# LB_BIT_i21_MICROPHONE-v03_rev4_4.net
KiCad netlist of a schematic drawn in EAGLE
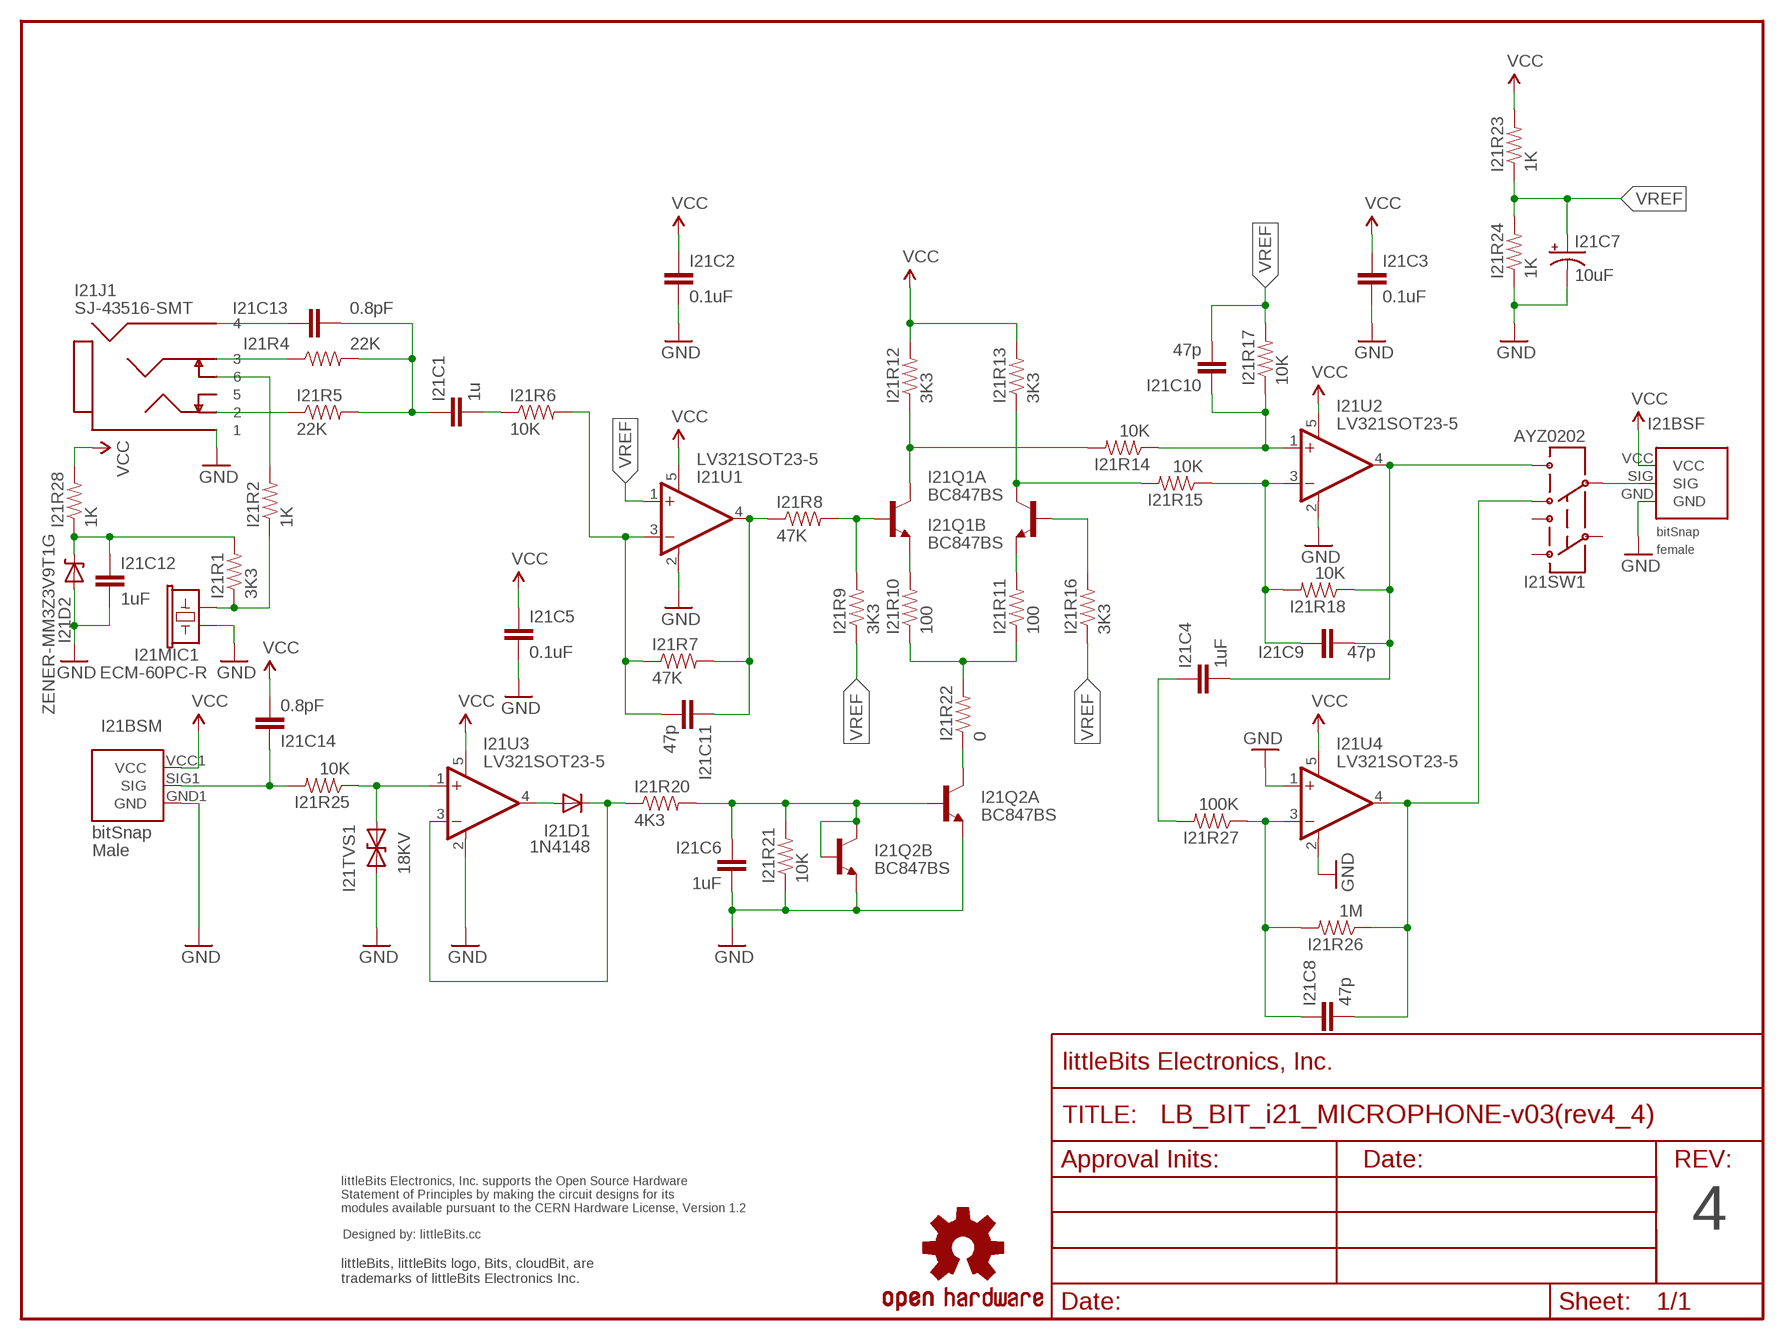
[diagram p0: schematic, sheet 1]

(export (version "E")
  (design (tool "Eeschema 10.0.6"))
  (components
    (comp (ref "I21BSF")
      (value "BITSNAP_V03_FEMALE")
      (footprint "eagle-import:BITSNAP_V03_FEMALE")
      (libsource (lib "eagle-import") (part "BITSNAP_V03_FEMALE"))
    )
    (comp (ref "I21BSM")
      (value "BITSNAP_V03_MALE")
      (footprint "eagle-import:BITSNAP_V03_MALE")
      (libsource (lib "eagle-import") (part "BITSNAP_V03_MALE"))
    )
    (comp (ref "I21C1")
      (value "1u")
      (footprint "eagle-import:CAP-0603")
      (libsource (lib "eagle-import") (part "CAPCAP-0603"))
    )
    (comp (ref "I21C2")
      (value "0.1uF")
      (footprint "eagle-import:CAP-0603")
      (libsource (lib "eagle-import") (part "CAPCAP-0603"))
    )
    (comp (ref "I21C3")
      (value "0.1uF")
      (footprint "eagle-import:CAP-0603")
      (libsource (lib "eagle-import") (part "CAPCAP-0603"))
    )
    (comp (ref "I21C4")
      (value "1uF")
      (footprint "eagle-import:CAP-0603")
      (libsource (lib "eagle-import") (part "CAPCAP-0603"))
    )
    (comp (ref "I21C5")
      (value "0.1uF")
      (footprint "eagle-import:CAP-0603")
      (libsource (lib "eagle-import") (part "CAPCAP-0603"))
    )
    (comp (ref "I21C6")
      (value "1uF")
      (footprint "eagle-import:CAP-0603")
      (libsource (lib "eagle-import") (part "CAPCAP-0603"))
    )
    (comp (ref "I21C7")
      (value "10uF")
      (footprint "eagle-import:EIA3216")
      (libsource (lib "eagle-import") (part "CAP_POL3216"))
    )
    (comp (ref "I21C8")
      (value "47p")
      (footprint "eagle-import:CAP-0603")
      (libsource (lib "eagle-import") (part "CAPCAP-0603"))
    )
    (comp (ref "I21C9")
      (value "47p")
      (footprint "eagle-import:CAP-0603")
      (libsource (lib "eagle-import") (part "CAPCAP-0603"))
    )
    (comp (ref "I21C10")
      (value "47p")
      (footprint "eagle-import:CAP-0603")
      (libsource (lib "eagle-import") (part "CAPCAP-0603"))
    )
    (comp (ref "I21C11")
      (value "47p")
      (footprint "eagle-import:CAP-0603")
      (libsource (lib "eagle-import") (part "CAPCAP-0603"))
    )
    (comp (ref "I21C12")
      (value "1uF")
      (footprint "eagle-import:CAP-0603")
      (libsource (lib "eagle-import") (part "CAPCAP-0603"))
    )
    (comp (ref "I21C13")
      (value "0.8pF")
      (footprint "eagle-import:CAP-0603")
      (libsource (lib "eagle-import") (part "CAPCAP-0603"))
    )
    (comp (ref "I21C14")
      (value "0.8pF")
      (footprint "eagle-import:CAP-0603")
      (libsource (lib "eagle-import") (part "CAPCAP-0603"))
    )
    (comp (ref "I21D1")
      (value "1N4148")
      (footprint "eagle-import:SOD-323")
      (libsource (lib "eagle-import") (part "DIODESOD"))
    )
    (comp (ref "I21D2")
      (value "ZENER-MM3Z3V9T1G")
      (footprint "eagle-import:SOD-323")
      (libsource (lib "eagle-import") (part "DIODE-ZENER-BZT52"))
    )
    (comp (ref "I21J1")
      (value "SJ-43516-SMT")
      (footprint "eagle-import:CUI-SJ-4351")
      (libsource (lib "eagle-import") (part "JACK-PHONO-4COND-SW"))
    )
    (comp (ref "I21MIC1")
      (value "ECM-60PC-R")
      (footprint "eagle-import:MIC9.7MM")
      (libsource (lib "eagle-import") (part "MIC9.7MM"))
    )
    (comp (ref "I21Q1")
      (value "BC847BS")
      (footprint "eagle-import:SOT-363_PHILLIPS")
      (libsource (lib "eagle-import") (part "TRANS-BJT_NPN-DUAL-BC847BS"))
    )
    (comp (ref "I21Q2")
      (value "BC847BS")
      (footprint "eagle-import:SOT-363_PHILLIPS")
      (libsource (lib "eagle-import") (part "TRANS-BJT_NPN-DUAL-BC847BS"))
    )
    (comp (ref "I21R1")
      (value "3K3")
      (footprint "eagle-import:RES-0603")
      (libsource (lib "eagle-import") (part "RESISTOR0603"))
    )
    (comp (ref "I21R2")
      (value "1K")
      (footprint "eagle-import:RES-0603")
      (libsource (lib "eagle-import") (part "RESISTOR0603"))
    )
    (comp (ref "I21R4")
      (value "22K")
      (footprint "eagle-import:RES-0603")
      (libsource (lib "eagle-import") (part "RESISTOR0603"))
    )
    (comp (ref "I21R5")
      (value "22K")
      (footprint "eagle-import:RES-0603")
      (libsource (lib "eagle-import") (part "RESISTOR0603"))
    )
    (comp (ref "I21R6")
      (value "10K")
      (footprint "eagle-import:RES-0603")
      (libsource (lib "eagle-import") (part "RESISTOR0603"))
    )
    (comp (ref "I21R7")
      (value "47K")
      (footprint "eagle-import:RES-0603")
      (libsource (lib "eagle-import") (part "RESISTOR0603"))
    )
    (comp (ref "I21R8")
      (value "47K")
      (footprint "eagle-import:RES-0603")
      (libsource (lib "eagle-import") (part "RESISTOR0603"))
    )
    (comp (ref "I21R9")
      (value "3K3")
      (footprint "eagle-import:RES-0603")
      (libsource (lib "eagle-import") (part "RESISTOR0603"))
    )
    (comp (ref "I21R10")
      (value "100")
      (footprint "eagle-import:RES-0603")
      (libsource (lib "eagle-import") (part "RESISTOR0603"))
    )
    (comp (ref "I21R11")
      (value "100")
      (footprint "eagle-import:RES-0603")
      (libsource (lib "eagle-import") (part "RESISTOR0603"))
    )
    (comp (ref "I21R12")
      (value "3K3")
      (footprint "eagle-import:RES-0603")
      (libsource (lib "eagle-import") (part "RESISTOR0603"))
    )
    (comp (ref "I21R13")
      (value "3K3")
      (footprint "eagle-import:RES-0603")
      (libsource (lib "eagle-import") (part "RESISTOR0603"))
    )
    (comp (ref "I21R14")
      (value "10K")
      (footprint "eagle-import:RES-0603")
      (libsource (lib "eagle-import") (part "RESISTOR0603"))
    )
    (comp (ref "I21R15")
      (value "10K")
      (footprint "eagle-import:RES-0603")
      (libsource (lib "eagle-import") (part "RESISTOR0603"))
    )
    (comp (ref "I21R16")
      (value "3K3")
      (footprint "eagle-import:RES-0603")
      (libsource (lib "eagle-import") (part "RESISTOR0603"))
    )
    (comp (ref "I21R17")
      (value "10K")
      (footprint "eagle-import:RES-0603")
      (libsource (lib "eagle-import") (part "RESISTOR0603"))
    )
    (comp (ref "I21R18")
      (value "10K")
      (footprint "eagle-import:RES-0603")
      (libsource (lib "eagle-import") (part "RESISTOR0603"))
    )
    (comp (ref "I21R20")
      (value "4K3")
      (footprint "eagle-import:RES-0603")
      (libsource (lib "eagle-import") (part "RESISTOR0603"))
    )
    (comp (ref "I21R21")
      (value "10K")
      (footprint "eagle-import:RES-0603")
      (libsource (lib "eagle-import") (part "RESISTOR0603"))
    )
    (comp (ref "I21R22")
      (value "0")
      (footprint "eagle-import:RES-0603")
      (libsource (lib "eagle-import") (part "RESISTOR0603"))
    )
    (comp (ref "I21R23")
      (value "1K")
      (footprint "eagle-import:RES-0603")
      (libsource (lib "eagle-import") (part "RESISTOR0603"))
    )
    (comp (ref "I21R24")
      (value "1K")
      (footprint "eagle-import:RES-0603")
      (libsource (lib "eagle-import") (part "RESISTOR0603"))
    )
    (comp (ref "I21R25")
      (value "10K")
      (footprint "eagle-import:RES-0603")
      (libsource (lib "eagle-import") (part "RESISTOR0603"))
    )
    (comp (ref "I21R26")
      (value "1M")
      (footprint "eagle-import:RES-0603")
      (libsource (lib "eagle-import") (part "RESISTOR0603"))
    )
    (comp (ref "I21R27")
      (value "100K")
      (footprint "eagle-import:RES-0603")
      (libsource (lib "eagle-import") (part "RESISTOR0603"))
    )
    (comp (ref "I21R28")
      (value "1K")
      (footprint "eagle-import:RES-0603")
      (libsource (lib "eagle-import") (part "RESISTOR0603"))
    )
    (comp (ref "I21SW1")
      (value "AYZ0202")
      (footprint "eagle-import:AYZ0202")
      (libsource (lib "eagle-import") (part "AYZ0202"))
    )
    (comp (ref "I21TVS1")
      (value "18KV")
      (footprint "eagle-import:SOD-923")
      (fields (field (name "MPN") "ESD9B5.0ST5G"))
      (libsource (lib "eagle-import") (part "DIODE-TVSSOD-923"))
    )
    (comp (ref "I21U1")
      (value "LV321SOT23-5")
      (footprint "eagle-import:SOT23-5")
      (libsource (lib "eagle-import") (part "LV321SOT23-5"))
    )
    (comp (ref "I21U2")
      (value "LV321SOT23-5")
      (footprint "eagle-import:SOT23-5")
      (libsource (lib "eagle-import") (part "LV321SOT23-5"))
    )
    (comp (ref "I21U3")
      (value "LV321SOT23-5")
      (footprint "eagle-import:SOT23-5")
      (libsource (lib "eagle-import") (part "LV321SOT23-5"))
    )
    (comp (ref "I21U4")
      (value "LV321SOT23-5")
      (footprint "eagle-import:SOT23-5")
      (libsource (lib "eagle-import") (part "LV321SOT23-5"))
    )
    (comp (ref "U$3")
      (value "OSHWCREDIT")
      (footprint "eagle-import:OSHWCREDIT")
      (libsource (lib "eagle-import") (part "OSHWCREDIT"))
    )
    (comp (ref "U$4")
      (value "FRAME-LETTER-OHWOHW")
      (footprint "eagle-import:FABDWG01-OHW")
      (libsource (lib "eagle-import") (part "FRAME-LETTER-OHWOHW"))
    )
    (comp (ref "U$19")
      (value "OSHW-LOGOL")
      (footprint "eagle-import:OSHW-LOGO-L")
      (libsource (lib "eagle-import") (part "OSHW-LOGOL"))
    )
  )
  (nets
    (net (code "1") (name "GND") (class "Default")
      (node (ref "I21BSF") (pin "GND") (pinfunction "GND_GND") (pintype "bidirectional"))
      (node (ref "I21BSM") (pin "GND1") (pinfunction "GND_GND1") (pintype "bidirectional"))
      (node (ref "I21C12") (pin "2") (pinfunction "2_2") (pintype "passive"))
      (node (ref "I21C2") (pin "2") (pinfunction "2_2") (pintype "passive"))
      (node (ref "I21C3") (pin "2") (pinfunction "2_2") (pintype "passive"))
      (node (ref "I21C5") (pin "2") (pinfunction "2_2") (pintype "passive"))
      (node (ref "I21C6") (pin "2") (pinfunction "2_2") (pintype "passive"))
      (node (ref "I21C7") (pin "-") (pinfunction "-_-") (pintype "passive"))
      (node (ref "I21D2") (pin "2") (pinfunction "A_2") (pintype "passive"))
      (node (ref "I21J1") (pin "1") (pinfunction "1_1") (pintype "bidirectional"))
      (node (ref "I21MIC1") (pin "2") (pinfunction "2_2") (pintype "passive"))
      (node (ref "I21Q2") (pin "1") (pinfunction "E_1") (pintype "passive"))
      (node (ref "I21Q2") (pin "4") (pinfunction "E_4") (pintype "passive"))
      (node (ref "I21R21") (pin "1") (pinfunction "1_1") (pintype "passive"))
      (node (ref "I21R24") (pin "1") (pinfunction "1_1") (pintype "passive"))
      (node (ref "I21TVS1") (pin "1") (pinfunction "A_1") (pintype "passive"))
      (node (ref "I21U1") (pin "2") (pinfunction "V-_2") (pintype "power_in"))
      (node (ref "I21U2") (pin "2") (pinfunction "V-_2") (pintype "power_in"))
      (node (ref "I21U3") (pin "2") (pinfunction "V-_2") (pintype "power_in"))
      (node (ref "I21U4") (pin "1") (pinfunction "+IN_1") (pintype "input"))
      (node (ref "I21U4") (pin "2") (pinfunction "V-_2") (pintype "power_in"))
    )
    (net (code "2") (name "Net-(I21BSF-PadSIG)") (class "Default")
      (node (ref "I21BSF") (pin "SIG") (pinfunction "SIG_SIG") (pintype "bidirectional"))
      (node (ref "I21SW1") (pin "5") (pinfunction "5_5") (pintype "bidirectional"))
    )
    (net (code "3") (name "Net-(I21BSM-SIG)") (class "Default")
      (node (ref "I21BSM") (pin "SIG1") (pinfunction "SIG_SIG1") (pintype "bidirectional"))
      (node (ref "I21C14") (pin "1") (pinfunction "1_1") (pintype "passive"))
      (node (ref "I21R25") (pin "2") (pinfunction "2_2") (pintype "passive"))
    )
    (net (code "4") (name "Net-(I21C1-Pad1)") (class "Default")
      (node (ref "I21C1") (pin "1") (pinfunction "1_1") (pintype "passive"))
      (node (ref "I21C13") (pin "2") (pinfunction "2_2") (pintype "passive"))
      (node (ref "I21R4") (pin "2") (pinfunction "2_2") (pintype "passive"))
      (node (ref "I21R5") (pin "2") (pinfunction "2_2") (pintype "passive"))
    )
    (net (code "5") (name "Net-(I21C1-Pad2)") (class "Default")
      (node (ref "I21C1") (pin "2") (pinfunction "2_2") (pintype "passive"))
      (node (ref "I21R6") (pin "1") (pinfunction "1_1") (pintype "passive"))
    )
    (net (code "6") (name "Net-(I21C4-Pad1)") (class "Default")
      (node (ref "I21C4") (pin "1") (pinfunction "1_1") (pintype "passive"))
      (node (ref "I21R27") (pin "2") (pinfunction "2_2") (pintype "passive"))
    )
    (net (code "7") (name "Net-(I21C13-Pad1)") (class "Default")
      (node (ref "I21C13") (pin "1") (pinfunction "1_1") (pintype "passive"))
      (node (ref "I21J1") (pin "4") (pinfunction "4_4") (pintype "bidirectional"))
    )
    (net (code "8") (name "Net-(I21D1-A)") (class "Default")
      (node (ref "I21D1") (pin "2") (pinfunction "A_2") (pintype "passive"))
      (node (ref "I21U3") (pin "4") (pinfunction "OUT_4") (pintype "output"))
    )
    (net (code "9") (name "Net-(I21D1-C)") (class "Default")
      (node (ref "I21D1") (pin "1") (pinfunction "C_1") (pintype "passive"))
      (node (ref "I21R20") (pin "1") (pinfunction "1_1") (pintype "passive"))
      (node (ref "I21U3") (pin "3") (pinfunction "-IN_3") (pintype "input"))
    )
    (net (code "10") (name "Net-(I21D2-C)") (class "Default")
      (node (ref "I21C12") (pin "1") (pinfunction "1_1") (pintype "passive"))
      (node (ref "I21D2") (pin "1") (pinfunction "C_1") (pintype "passive"))
      (node (ref "I21R1") (pin "2") (pinfunction "2_2") (pintype "passive"))
      (node (ref "I21R28") (pin "1") (pinfunction "1_1") (pintype "passive"))
    )
    (net (code "11") (name "Net-(I21J1-Pad2)") (class "Default")
      (node (ref "I21J1") (pin "2") (pinfunction "2_2") (pintype "bidirectional"))
      (node (ref "I21R5") (pin "1") (pinfunction "1_1") (pintype "passive"))
    )
    (net (code "12") (name "Net-(I21J1-Pad3)") (class "Default")
      (node (ref "I21J1") (pin "3") (pinfunction "3_3") (pintype "bidirectional"))
      (node (ref "I21R4") (pin "1") (pinfunction "1_1") (pintype "passive"))
    )
    (net (code "13") (name "Net-(I21J1-Pad6)") (class "Default")
      (node (ref "I21J1") (pin "6") (pinfunction "6_6") (pintype "bidirectional"))
      (node (ref "I21R2") (pin "2") (pinfunction "2_2") (pintype "passive"))
    )
    (net (code "14") (name "Net-(I21MIC1-Pad1)") (class "Default")
      (node (ref "I21MIC1") (pin "1") (pinfunction "1_1") (pintype "passive"))
      (node (ref "I21R1") (pin "1") (pinfunction "1_1") (pintype "passive"))
      (node (ref "I21R2") (pin "1") (pinfunction "1_1") (pintype "passive"))
    )
    (net (code "15") (name "Net-(I21Q1A-B)") (class "Default")
      (node (ref "I21Q1") (pin "2") (pinfunction "B_2") (pintype "passive"))
      (node (ref "I21R8") (pin "2") (pinfunction "2_2") (pintype "passive"))
      (node (ref "I21R9") (pin "2") (pinfunction "2_2") (pintype "passive"))
    )
    (net (code "16") (name "Net-(I21Q1A-C)") (class "Default")
      (node (ref "I21Q1") (pin "6") (pinfunction "C_6") (pintype "passive"))
      (node (ref "I21R12") (pin "1") (pinfunction "1_1") (pintype "passive"))
      (node (ref "I21R14") (pin "2") (pinfunction "2_2") (pintype "passive"))
    )
    (net (code "17") (name "Net-(I21Q1A-E)") (class "Default")
      (node (ref "I21Q1") (pin "1") (pinfunction "E_1") (pintype "passive"))
      (node (ref "I21R10") (pin "2") (pinfunction "2_2") (pintype "passive"))
    )
    (net (code "18") (name "Net-(I21Q1B-B)") (class "Default")
      (node (ref "I21Q1") (pin "5") (pinfunction "B_5") (pintype "passive"))
      (node (ref "I21R16") (pin "2") (pinfunction "2_2") (pintype "passive"))
    )
    (net (code "19") (name "Net-(I21Q1B-C)") (class "Default")
      (node (ref "I21Q1") (pin "3") (pinfunction "C_3") (pintype "passive"))
      (node (ref "I21R13") (pin "1") (pinfunction "1_1") (pintype "passive"))
      (node (ref "I21R15") (pin "2") (pinfunction "2_2") (pintype "passive"))
    )
    (net (code "20") (name "Net-(I21Q1B-E)") (class "Default")
      (node (ref "I21Q1") (pin "4") (pinfunction "E_4") (pintype "passive"))
      (node (ref "I21R11") (pin "2") (pinfunction "2_2") (pintype "passive"))
    )
    (net (code "21") (name "Net-(I21Q2A-B)") (class "Default")
      (node (ref "I21C6") (pin "1") (pinfunction "1_1") (pintype "passive"))
      (node (ref "I21Q2") (pin "2") (pinfunction "B_2") (pintype "passive"))
      (node (ref "I21Q2") (pin "3") (pinfunction "C_3") (pintype "passive"))
      (node (ref "I21Q2") (pin "5") (pinfunction "B_5") (pintype "passive"))
      (node (ref "I21R20") (pin "2") (pinfunction "2_2") (pintype "passive"))
      (node (ref "I21R21") (pin "2") (pinfunction "2_2") (pintype "passive"))
    )
    (net (code "22") (name "Net-(I21Q2A-C)") (class "Default")
      (node (ref "I21Q2") (pin "6") (pinfunction "C_6") (pintype "passive"))
      (node (ref "I21R22") (pin "1") (pinfunction "1_1") (pintype "passive"))
    )
    (net (code "23") (name "Net-(I21R10-Pad1)") (class "Default")
      (node (ref "I21R10") (pin "1") (pinfunction "1_1") (pintype "passive"))
      (node (ref "I21R11") (pin "1") (pinfunction "1_1") (pintype "passive"))
      (node (ref "I21R22") (pin "2") (pinfunction "2_2") (pintype "passive"))
    )
    (net (code "24") (name "Net-(I21TVS1-C)") (class "Default")
      (node (ref "I21R25") (pin "1") (pinfunction "1_1") (pintype "passive"))
      (node (ref "I21TVS1") (pin "2") (pinfunction "C_2") (pintype "passive"))
      (node (ref "I21U3") (pin "1") (pinfunction "+IN_1") (pintype "input"))
    )
    (net (code "25") (name "Net-(I21U1--IN)") (class "Default")
      (node (ref "I21C11") (pin "2") (pinfunction "2_2") (pintype "passive"))
      (node (ref "I21R6") (pin "2") (pinfunction "2_2") (pintype "passive"))
      (node (ref "I21R7") (pin "1") (pinfunction "1_1") (pintype "passive"))
      (node (ref "I21U1") (pin "3") (pinfunction "-IN_3") (pintype "input"))
    )
    (net (code "26") (name "Net-(I21U1-OUT)") (class "Default")
      (node (ref "I21C11") (pin "1") (pinfunction "1_1") (pintype "passive"))
      (node (ref "I21R7") (pin "2") (pinfunction "2_2") (pintype "passive"))
      (node (ref "I21R8") (pin "1") (pinfunction "1_1") (pintype "passive"))
      (node (ref "I21U1") (pin "4") (pinfunction "OUT_4") (pintype "output"))
    )
    (net (code "27") (name "Net-(I21U2-+IN)") (class "Default")
      (node (ref "I21C10") (pin "1") (pinfunction "1_1") (pintype "passive"))
      (node (ref "I21R14") (pin "1") (pinfunction "1_1") (pintype "passive"))
      (node (ref "I21R17") (pin "1") (pinfunction "1_1") (pintype "passive"))
      (node (ref "I21U2") (pin "1") (pinfunction "+IN_1") (pintype "input"))
    )
    (net (code "28") (name "Net-(I21U2--IN)") (class "Default")
      (node (ref "I21C9") (pin "1") (pinfunction "1_1") (pintype "passive"))
      (node (ref "I21R15") (pin "1") (pinfunction "1_1") (pintype "passive"))
      (node (ref "I21R18") (pin "2") (pinfunction "2_2") (pintype "passive"))
      (node (ref "I21U2") (pin "3") (pinfunction "-IN_3") (pintype "input"))
    )
    (net (code "29") (name "Net-(I21U2-OUT)") (class "Default")
      (node (ref "I21C4") (pin "2") (pinfunction "2_2") (pintype "passive"))
      (node (ref "I21C9") (pin "2") (pinfunction "2_2") (pintype "passive"))
      (node (ref "I21R18") (pin "1") (pinfunction "1_1") (pintype "passive"))
      (node (ref "I21SW1") (pin "6") (pinfunction "6_6") (pintype "bidirectional"))
      (node (ref "I21U2") (pin "4") (pinfunction "OUT_4") (pintype "output"))
    )
    (net (code "30") (name "Net-(I21U4--IN)") (class "Default")
      (node (ref "I21C8") (pin "1") (pinfunction "1_1") (pintype "passive"))
      (node (ref "I21R26") (pin "2") (pinfunction "2_2") (pintype "passive"))
      (node (ref "I21R27") (pin "1") (pinfunction "1_1") (pintype "passive"))
      (node (ref "I21U4") (pin "3") (pinfunction "-IN_3") (pintype "input"))
    )
    (net (code "31") (name "Net-(I21U4-OUT)") (class "Default")
      (node (ref "I21C8") (pin "2") (pinfunction "2_2") (pintype "passive"))
      (node (ref "I21R26") (pin "1") (pinfunction "1_1") (pintype "passive"))
      (node (ref "I21SW1") (pin "4") (pinfunction "4_4") (pintype "bidirectional"))
      (node (ref "I21U4") (pin "4") (pinfunction "OUT_4") (pintype "output"))
    )
    (net (code "32") (name "VCC") (class "Default")
      (node (ref "I21BSF") (pin "VCC") (pinfunction "VCC_VCC") (pintype "bidirectional"))
      (node (ref "I21BSM") (pin "VCC1") (pinfunction "VCC_VCC1") (pintype "bidirectional"))
      (node (ref "I21C14") (pin "2") (pinfunction "2_2") (pintype "passive"))
      (node (ref "I21C2") (pin "1") (pinfunction "1_1") (pintype "passive"))
      (node (ref "I21C3") (pin "1") (pinfunction "1_1") (pintype "passive"))
      (node (ref "I21C5") (pin "1") (pinfunction "1_1") (pintype "passive"))
      (node (ref "I21R12") (pin "2") (pinfunction "2_2") (pintype "passive"))
      (node (ref "I21R13") (pin "2") (pinfunction "2_2") (pintype "passive"))
      (node (ref "I21R23") (pin "2") (pinfunction "2_2") (pintype "passive"))
      (node (ref "I21R28") (pin "2") (pinfunction "2_2") (pintype "passive"))
      (node (ref "I21U1") (pin "5") (pinfunction "V+_5") (pintype "power_in"))
      (node (ref "I21U2") (pin "5") (pinfunction "V+_5") (pintype "power_in"))
      (node (ref "I21U3") (pin "5") (pinfunction "V+_5") (pintype "power_in"))
      (node (ref "I21U4") (pin "5") (pinfunction "V+_5") (pintype "power_in"))
    )
    (net (code "33") (name "VREF") (class "Default")
      (node (ref "I21C10") (pin "2") (pinfunction "2_2") (pintype "passive"))
      (node (ref "I21C7") (pin "+") (pinfunction "+_+") (pintype "passive"))
      (node (ref "I21R16") (pin "1") (pinfunction "1_1") (pintype "passive"))
      (node (ref "I21R17") (pin "2") (pinfunction "2_2") (pintype "passive"))
      (node (ref "I21R23") (pin "1") (pinfunction "1_1") (pintype "passive"))
      (node (ref "I21R24") (pin "2") (pinfunction "2_2") (pintype "passive"))
      (node (ref "I21R9") (pin "1") (pinfunction "1_1") (pintype "passive"))
      (node (ref "I21U1") (pin "1") (pinfunction "+IN_1") (pintype "input"))
    )
    (net (code "34") (name "unconnected-(I21J1-Pad5)") (class "Default")
      (node (ref "I21J1") (pin "5") (pinfunction "5_5") (pintype "bidirectional"))
    )
    (net (code "35") (name "unconnected-(I21SW1-Pad1)") (class "Default")
      (node (ref "I21SW1") (pin "1") (pinfunction "1_1") (pintype "bidirectional"))
    )
    (net (code "36") (name "unconnected-(I21SW1-Pad2)") (class "Default")
      (node (ref "I21SW1") (pin "2") (pinfunction "2_2") (pintype "bidirectional"))
    )
    (net (code "37") (name "unconnected-(I21SW1-Pad3)") (class "Default")
      (node (ref "I21SW1") (pin "3") (pinfunction "3_3") (pintype "bidirectional"))
    )
  )
)
